# Pg6-Power_supply_3.net
KiCad netlist of a schematic drawn in Altium Designer
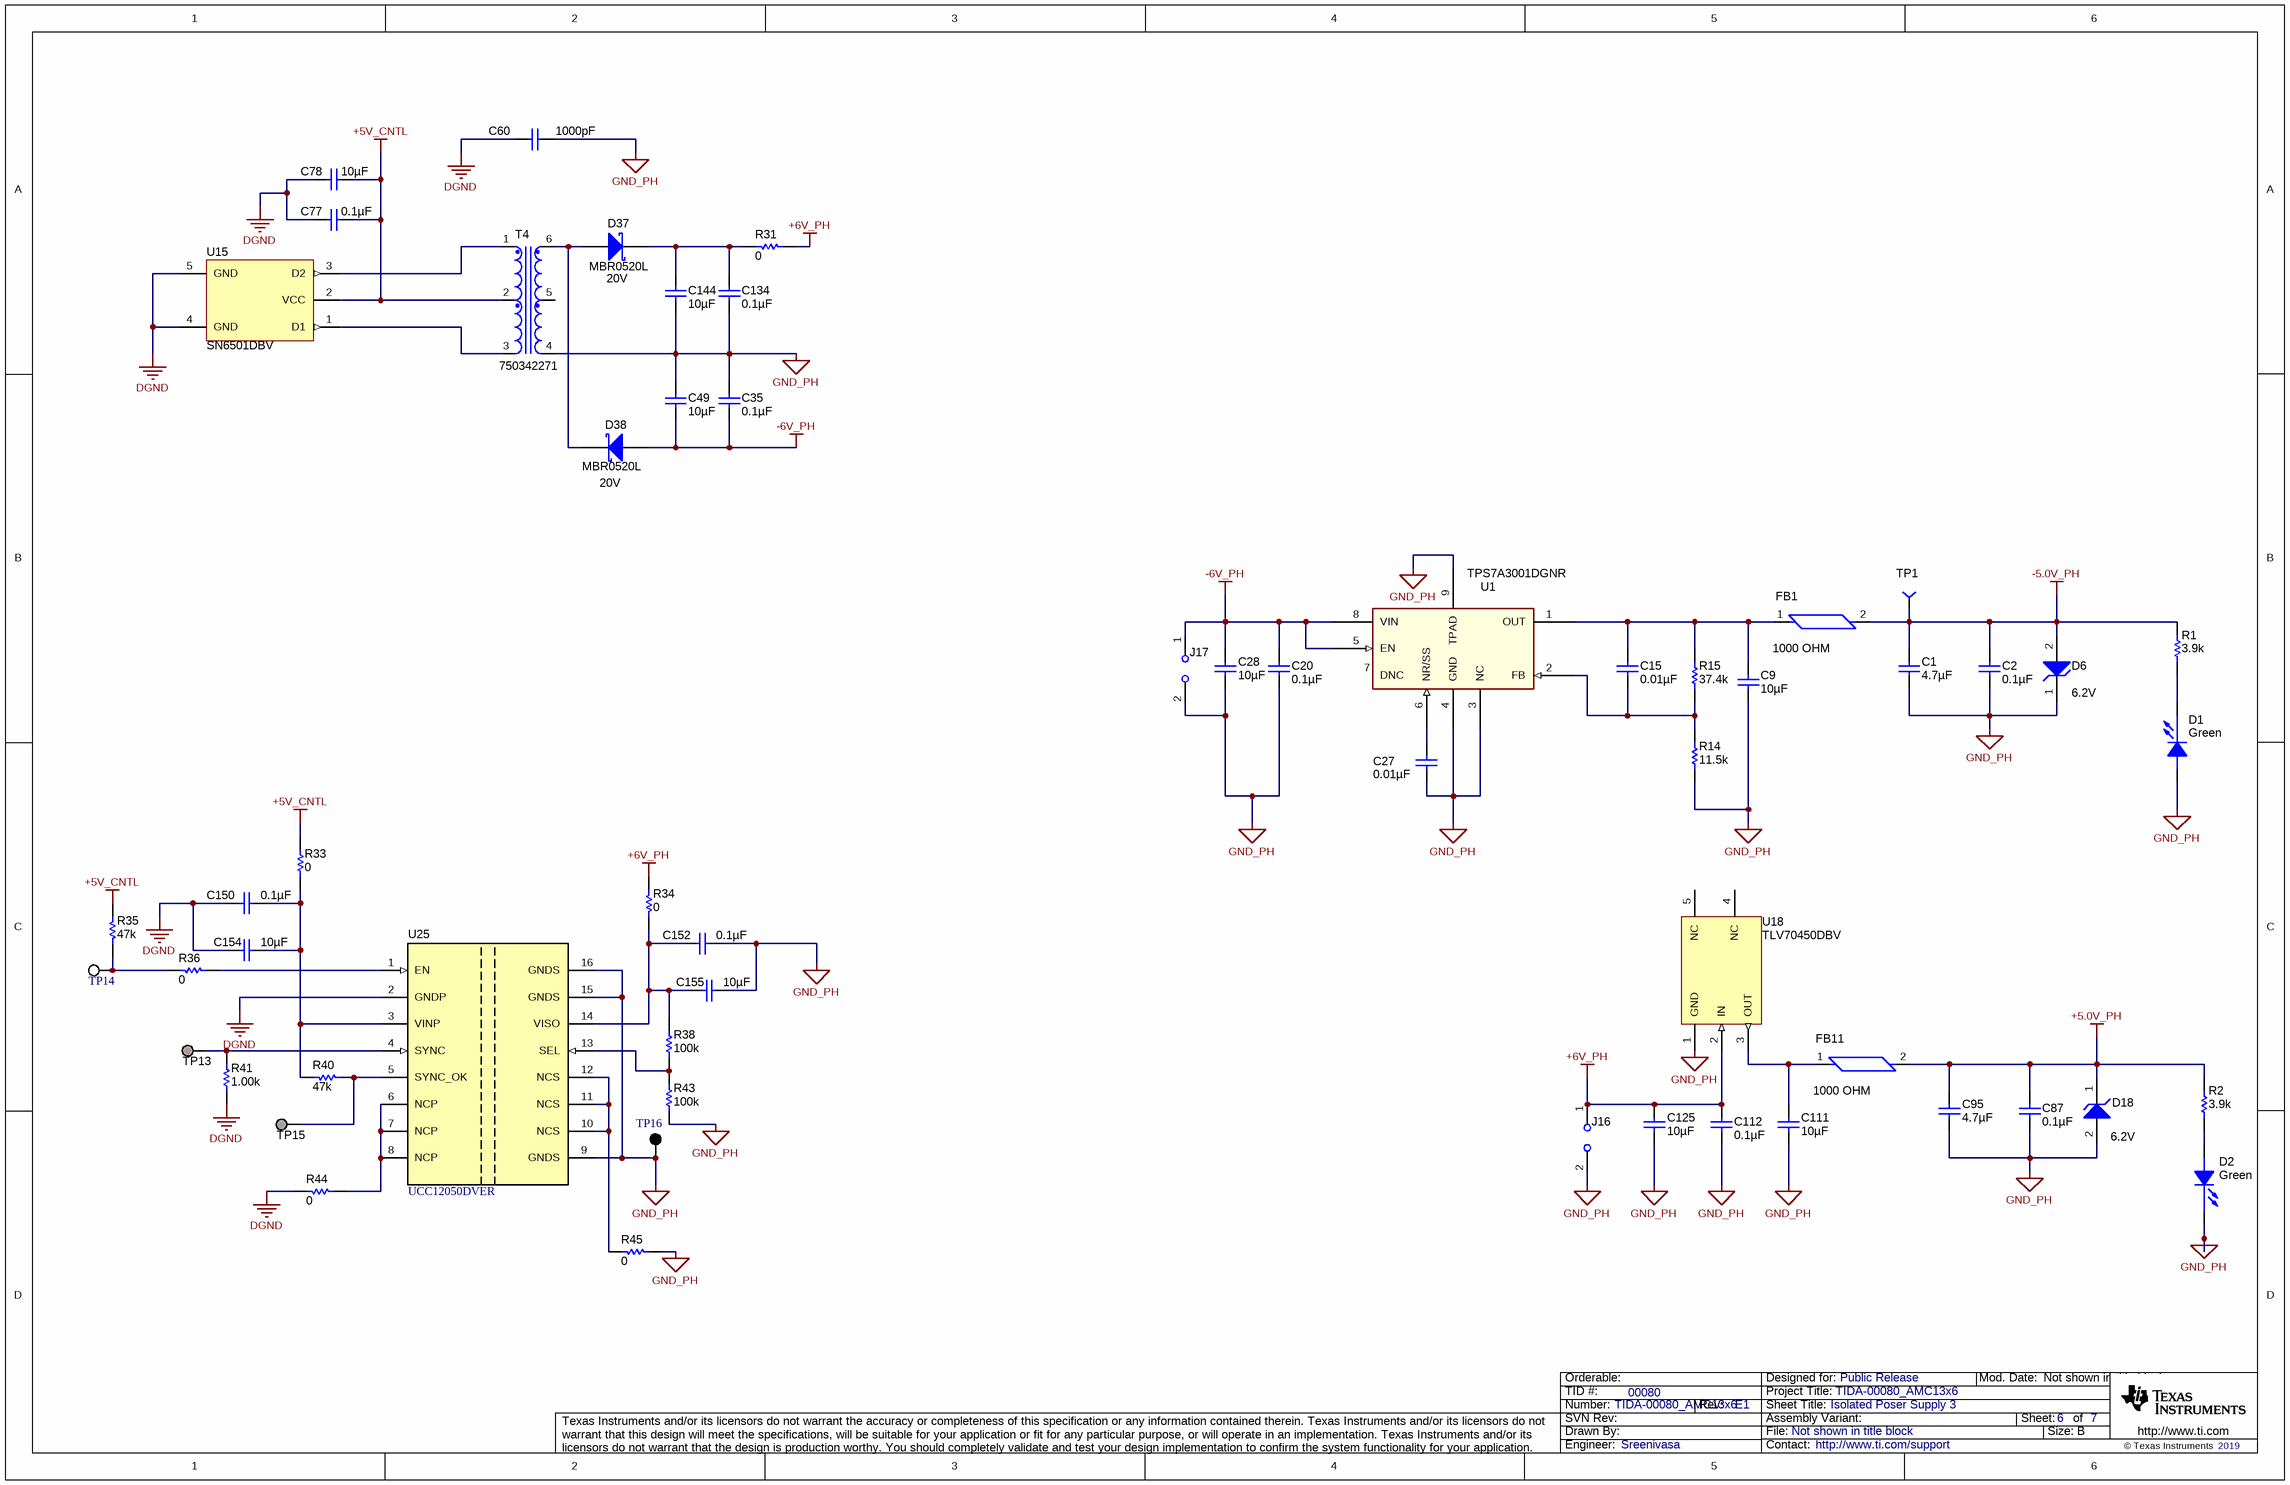
[diagram p0: Pg6-Power supply 3.SchDoc]

(export (version "E")
  (design (tool "Eeschema 10.0.6"))
  (components
    (comp (ref "C1")
      (value "~")
      (footprint "ISE_MCS_SDM_E1_20MAY:0805_HV")
      (description "CAP, CERM, 4.7uF, 50V, +/-10%, X5R, 0805")
      (fields
        (field (name "PARTNUMBER") "C2012X5R1H475K125AB")
        (field (name "VALUEDISPLAYED") "4.7µF")
        (field (name "MANUFACTURER") "TDK")
        (field (name "PUBLISHER") "Texas Instruments")
      )
      (libsource (lib "Capacitor_Ceramic") (part "C2012X5R1H475K125AB"))
    )
    (comp (ref "C2")
      (value "~")
      (footprint "ISE_MCS_SDM_E1_20MAY:0603")
      (description "CAP, CERM, 0.1uF, 50V, +/-10%, X7R, 0603")
      (fields
        (field (name "PARTNUMBER") "C0603C104K5RACTU")
        (field (name "VALUEDISPLAYED") "0.1µF")
        (field (name "MANUFACTURER") "Kemet")
        (field (name "PUBLISHER") "Texas Instruments")
      )
      (libsource (lib "Capacitor_Ceramic") (part "C0603C104K5RACTU"))
    )
    (comp (ref "C9")
      (value "~")
      (footprint "ISE_MCS_SDM_E1_20MAY:1210")
      (description "CAP, CERM, 10uF, 35V, +/-20%, X7R, 1210")
      (fields
        (field (name "PARTNUMBER") "GMK325AB7106MM-T")
        (field (name "VALUEDISPLAYED") "10µF")
        (field (name "MANUFACTURER") "Taiyo Yuden")
        (field (name "PUBLISHER") "Texas Instruments")
      )
      (libsource (lib "Capacitor_Ceramic") (part "GMK325AB7106MM-T"))
    )
    (comp (ref "C15")
      (value "~")
      (footprint "ISE_MCS_SDM_E1_20MAY:0603")
      (description "CAP, CERM, 0.01uF, 100V, +/-5%, X7R, 0603")
      (fields
        (field (name "PARTNUMBER") "06031C103J4Z4A")
        (field (name "VALUEDISPLAYED") "0.01µF")
        (field (name "MANUFACTURER") "AVX")
        (field (name "PUBLISHER") "Texas Instruments")
      )
      (libsource (lib "Capacitor_Ceramic") (part "06031C103J4Z4A"))
    )
    (comp (ref "C20")
      (value "~")
      (footprint "ISE_MCS_SDM_E1_20MAY:0603")
      (description "CAP, CERM, 0.1uF, 50V, +/-10%, X7R, 0603")
      (fields
        (field (name "PARTNUMBER") "C0603C104K5RACTU")
        (field (name "VALUEDISPLAYED") "0.1µF")
        (field (name "MANUFACTURER") "Kemet")
        (field (name "PUBLISHER") "Texas Instruments")
      )
      (libsource (lib "Capacitor_Ceramic") (part "C0603C104K5RACTU"))
    )
    (comp (ref "C27")
      (value "~")
      (footprint "ISE_MCS_SDM_E1_20MAY:0603")
      (description "CAP, CERM, 0.01uF, 100V, +/-5%, X7R, 0603")
      (fields
        (field (name "PARTNUMBER") "06031C103J4Z4A")
        (field (name "VALUEDISPLAYED") "0.01µF")
        (field (name "MANUFACTURER") "AVX")
        (field (name "PUBLISHER") "Texas Instruments")
      )
      (libsource (lib "Capacitor_Ceramic") (part "06031C103J4Z4A"))
    )
    (comp (ref "C28")
      (value "~")
      (footprint "ISE_MCS_SDM_E1_20MAY:1210")
      (description "CAP, CERM, 10uF, 35V, +/-20%, X7R, 1210")
      (fields
        (field (name "PARTNUMBER") "GMK325AB7106MM-T")
        (field (name "VALUEDISPLAYED") "10µF")
        (field (name "MANUFACTURER") "Taiyo Yuden")
        (field (name "PUBLISHER") "Texas Instruments")
      )
      (libsource (lib "Capacitor_Ceramic") (part "GMK325AB7106MM-T"))
    )
    (comp (ref "C35")
      (value "~")
      (footprint "ISE_MCS_SDM_E1_20MAY:0603")
      (description "CAP, CERM, 0.1uF, 50V, +/-10%, X7R, 0603")
      (fields
        (field (name "PARTNUMBER") "C0603C104K5RACTU")
        (field (name "VALUEDISPLAYED") "0.1µF")
        (field (name "MANUFACTURER") "Kemet")
        (field (name "PUBLISHER") "Texas Instruments")
      )
      (libsource (lib "Capacitor_Ceramic") (part "C0603C104K5RACTU"))
    )
    (comp (ref "C49")
      (value "~")
      (footprint "ISE_MCS_SDM_E1_20MAY:1210")
      (description "CAP, CERM, 10uF, 35V, +/-20%, X7R, 1210")
      (fields
        (field (name "PARTNUMBER") "GMK325AB7106MM-T")
        (field (name "VALUEDISPLAYED") "10µF")
        (field (name "MANUFACTURER") "Taiyo Yuden")
        (field (name "PUBLISHER") "Texas Instruments")
      )
      (libsource (lib "Capacitor_Ceramic") (part "GMK325AB7106MM-T"))
    )
    (comp (ref "C60")
      (value "1000pF")
      (footprint "CAP_200mil")
      (description "CAP CER 1000PF 1KV 10% RADIAL")
      (fields
        (field (name "PARTNUMBER") "S102K29Y5PN63J5R")
        (field (name "MANUFACTURER") "Vishay BC Components")
        (field (name "PUBLISHER") "Texas Instruments")
      )
      (libsource (lib "TI-INDIA-ALTIUM") (part "202R18W102KV4E"))
    )
    (comp (ref "C77")
      (value "~")
      (footprint "ISE_MCS_SDM_E1_20MAY:0603")
      (description "CAP, CERM, 0.1uF, 50V, +/-10%, X7R, 0603")
      (fields
        (field (name "PARTNUMBER") "C0603C104K5RACTU")
        (field (name "VALUEDISPLAYED") "0.1µF")
        (field (name "MANUFACTURER") "Kemet")
        (field (name "PUBLISHER") "Texas Instruments")
      )
      (libsource (lib "Capacitor_Ceramic") (part "C0603C104K5RACTU"))
    )
    (comp (ref "C78")
      (value "~")
      (footprint "ISE_MCS_SDM_E1_20MAY:1210")
      (description "CAP, CERM, 10uF, 35V, +/-20%, X7R, 1210")
      (fields
        (field (name "PARTNUMBER") "GMK325AB7106MM-T")
        (field (name "VALUEDISPLAYED") "10µF")
        (field (name "MANUFACTURER") "Taiyo Yuden")
        (field (name "PUBLISHER") "Texas Instruments")
      )
      (libsource (lib "Capacitor_Ceramic") (part "GMK325AB7106MM-T"))
    )
    (comp (ref "C87")
      (value "~")
      (footprint "ISE_MCS_SDM_E1_20MAY:0603")
      (description "CAP, CERM, 0.1uF, 50V, +/-10%, X7R, 0603")
      (fields
        (field (name "PARTNUMBER") "C0603C104K5RACTU")
        (field (name "VALUEDISPLAYED") "0.1µF")
        (field (name "MANUFACTURER") "Kemet")
        (field (name "PUBLISHER") "Texas Instruments")
      )
      (libsource (lib "Capacitor_Ceramic") (part "C0603C104K5RACTU"))
    )
    (comp (ref "C95")
      (value "~")
      (footprint "ISE_MCS_SDM_E1_20MAY:0805_HV")
      (description "CAP, CERM, 4.7uF, 50V, +/-10%, X5R, 0805")
      (fields
        (field (name "PARTNUMBER") "C2012X5R1H475K125AB")
        (field (name "VALUEDISPLAYED") "4.7µF")
        (field (name "MANUFACTURER") "TDK")
        (field (name "PUBLISHER") "Texas Instruments")
      )
      (libsource (lib "Capacitor_Ceramic") (part "C2012X5R1H475K125AB"))
    )
    (comp (ref "C111")
      (value "~")
      (footprint "ISE_MCS_SDM_E1_20MAY:1210")
      (description "CAP, CERM, 10uF, 35V, +/-20%, X7R, 1210")
      (fields
        (field (name "PARTNUMBER") "GMK325AB7106MM-T")
        (field (name "VALUEDISPLAYED") "10µF")
        (field (name "MANUFACTURER") "Taiyo Yuden")
        (field (name "PUBLISHER") "Texas Instruments")
      )
      (libsource (lib "Capacitor_Ceramic") (part "GMK325AB7106MM-T"))
    )
    (comp (ref "C112")
      (value "~")
      (footprint "ISE_MCS_SDM_E1_20MAY:0603")
      (description "CAP, CERM, 0.1uF, 50V, +/-10%, X7R, 0603")
      (fields
        (field (name "PARTNUMBER") "C0603C104K5RACTU")
        (field (name "VALUEDISPLAYED") "0.1µF")
        (field (name "MANUFACTURER") "Kemet")
        (field (name "PUBLISHER") "Texas Instruments")
      )
      (libsource (lib "Capacitor_Ceramic") (part "C0603C104K5RACTU"))
    )
    (comp (ref "C125")
      (value "~")
      (footprint "ISE_MCS_SDM_E1_20MAY:1210")
      (description "CAP, CERM, 10uF, 35V, +/-20%, X7R, 1210")
      (fields
        (field (name "PARTNUMBER") "GMK325AB7106MM-T")
        (field (name "VALUEDISPLAYED") "10µF")
        (field (name "MANUFACTURER") "Taiyo Yuden")
        (field (name "PUBLISHER") "Texas Instruments")
      )
      (libsource (lib "Capacitor_Ceramic") (part "GMK325AB7106MM-T"))
    )
    (comp (ref "C134")
      (value "~")
      (footprint "ISE_MCS_SDM_E1_20MAY:0603")
      (description "CAP, CERM, 0.1uF, 50V, +/-10%, X7R, 0603")
      (fields
        (field (name "PARTNUMBER") "C0603C104K5RACTU")
        (field (name "VALUEDISPLAYED") "0.1µF")
        (field (name "MANUFACTURER") "Kemet")
        (field (name "PUBLISHER") "Texas Instruments")
      )
      (libsource (lib "Capacitor_Ceramic") (part "C0603C104K5RACTU"))
    )
    (comp (ref "C144")
      (value "~")
      (footprint "ISE_MCS_SDM_E1_20MAY:1210")
      (description "CAP, CERM, 10uF, 35V, +/-20%, X7R, 1210")
      (fields
        (field (name "PARTNUMBER") "GMK325AB7106MM-T")
        (field (name "VALUEDISPLAYED") "10µF")
        (field (name "MANUFACTURER") "Taiyo Yuden")
        (field (name "PUBLISHER") "Texas Instruments")
      )
      (libsource (lib "Capacitor_Ceramic") (part "GMK325AB7106MM-T"))
    )
    (comp (ref "C150")
      (value "C0603C104K5RACTU")
      (footprint "0603")
      (description "CAP, CERM, 0.1uF, 50V, +/-10%, X7R, 0603")
      (fields
        (field (name "VALUEDISPLAYED") "0.1µF")
        (field (name "MANUFACTURER") "Kemet")
        (field (name "PUBLISHER") "Texas Instruments")
      )
      (libsource (lib "Capacitor_Ceramic") (part "C0603C104K5RACTU"))
    )
    (comp (ref "C152")
      (value "C0603C104K5RACTU")
      (footprint "0603")
      (description "CAP, CERM, 0.1uF, 50V, +/-10%, X7R, 0603")
      (fields
        (field (name "VALUEDISPLAYED") "0.1µF")
        (field (name "MANUFACTURER") "Kemet")
        (field (name "PUBLISHER") "Texas Instruments")
      )
      (libsource (lib "Capacitor_Ceramic") (part "C0603C104K5RACTU"))
    )
    (comp (ref "C154")
      (value "GRM31CR61H106KA12L")
      (footprint "1206_180")
      (description "CAP, CERM, 10 µF, 50 V, +/- 10%, X5R, 1206")
      (fields
        (field (name "VALUEDISPLAYED") "10µF")
        (field (name "MANUFACTURER") "MuRata")
        (field (name "PUBLISHER") "Texas Instruments")
      )
      (libsource (lib "Capacitor_Ceramic") (part "GRM31CR61H106KA12L"))
    )
    (comp (ref "C155")
      (value "GRM31CR61H106KA12L")
      (footprint "1206_180")
      (description "CAP, CERM, 10 µF, 50 V, +/- 10%, X5R, 1206")
      (fields
        (field (name "VALUEDISPLAYED") "10µF")
        (field (name "MANUFACTURER") "MuRata")
        (field (name "PUBLISHER") "Texas Instruments")
      )
      (libsource (lib "Capacitor_Ceramic") (part "GRM31CR61H106KA12L"))
    )
    (comp (ref "D1")
      (value "Green")
      (footprint "ISE_MCS_SDM_E1_20MAY:LED0603AA")
      (description "LED SmartLED Green 570NM")
      (fields
        (field (name "PARTNUMBER") "LG L29K-G2J1-24-Z")
        (field (name "MANUFACTURER") "OSRAM")
        (field (name "PUBLISHER") "TI")
        (field (name "SYMBOLCREATOR") "x0120606")
      )
      (libsource (lib "TI-INDIA-ALTIUM") (part "LED_LG L29K-G2J1-24-Z"))
    )
    (comp (ref "D2")
      (value "Green")
      (footprint "ISE_MCS_SDM_E1_20MAY:LED0603AA")
      (description "LED SmartLED Green 570NM")
      (fields
        (field (name "PARTNUMBER") "LG L29K-G2J1-24-Z")
        (field (name "MANUFACTURER") "OSRAM")
        (field (name "PUBLISHER") "TI")
        (field (name "SYMBOLCREATOR") "x0120606")
      )
      (libsource (lib "TI-INDIA-ALTIUM") (part "LED_LG L29K-G2J1-24-Z"))
    )
    (comp (ref "D6")
      (value "6.2V")
      (footprint "ISE_MCS_SDM_E1_20MAY:powerDI123")
      (description "Diode, Zener, 6.2V, 1W, PowerDI123")
      (fields
        (field (name "PARTNUMBER") "DFLZ6V2-7")
        (field (name "MANUFACTURER") "Diodes Inc.")
        (field (name "PUBLISHER") "Texas Instruments")
      )
      (libsource (lib "ZenerDiodes") (part "DFLZ6V2-7"))
    )
    (comp (ref "D18")
      (value "6.2V")
      (footprint "ISE_MCS_SDM_E1_20MAY:powerDI123")
      (description "Diode, Zener, 6.2V, 1W, PowerDI123")
      (fields
        (field (name "PARTNUMBER") "DFLZ6V2-7")
        (field (name "MANUFACTURER") "Diodes Inc.")
        (field (name "PUBLISHER") "Texas Instruments")
      )
      (libsource (lib "ZenerDiodes") (part "DFLZ6V2-7"))
    )
    (comp (ref "D37")
      (value "MBR0520L")
      (footprint "ISE_MCS_SDM_E1_20MAY:SOD-123")
      (description "Diode, Schottky, 20V, 0.5A, SOD-123")
      (fields
        (field (name "ALTIUM_VALUE") "20V")
        (field (name "MANUFACTURER") "Fairchild Semiconductor")
        (field (name "PUBLISHER") "Texas Instruments")
      )
      (libsource (lib "Diode") (part "MBR0520LT1G"))
    )
    (comp (ref "D38")
      (value "MBR0520L")
      (footprint "ISE_MCS_SDM_E1_20MAY:SOD-123")
      (description "Diode, Schottky, 20V, 0.5A, SOD-123")
      (fields
        (field (name "ALTIUM_VALUE") "20V")
        (field (name "MANUFACTURER") "Fairchild Semiconductor")
        (field (name "PUBLISHER") "Texas Instruments")
      )
      (libsource (lib "Diode") (part "MBR0520LT1G"))
    )
    (comp (ref "FB1")
      (value "1000 OHM")
      (footprint "ISE_MCS_SDM_E1_20MAY:FB0603")
      (description "FERRITE CHIP 1000 OHM 300MA 0603")
      (fields
        (field (name "PARTNUMBER") "MMZ1608B102C")
        (field (name "MANUFACTURER") "TDK Corporation")
        (field (name "PUBLISHER") "TI")
      )
      (libsource (lib "TI-INDIA-ALTIUM") (part "MMZ1608B102C"))
    )
    (comp (ref "FB11")
      (value "1000 OHM")
      (footprint "ISE_MCS_SDM_E1_20MAY:FB0603")
      (description "FERRITE CHIP 1000 OHM 300MA 0603")
      (fields
        (field (name "PARTNUMBER") "MMZ1608B102C")
        (field (name "MANUFACTURER") "TDK Corporation")
        (field (name "PUBLISHER") "TI")
      )
      (libsource (lib "TI-INDIA-ALTIUM") (part "MMZ1608B102C"))
    )
    (comp (ref "J16")
      (value "~")
      (footprint "ISE_MCS_SDM_E1_20MAY:HDR100_1X2")
      (description "Header, Male 2-pin, 100mil spacing,")
      (fields (field (name "MANUFACTURER") "FCI") (field (name "PARTNUMBER") "68001-402HLF"))
      (libsource (lib "PADSlegacy_Hardware") (part "JUMPER_2X100MIL"))
    )
    (comp (ref "J17")
      (value "~")
      (footprint "ISE_MCS_SDM_E1_20MAY:HDR100_1X2")
      (description "Header, Male 2-pin, 100mil spacing,")
      (fields (field (name "MANUFACTURER") "FCI") (field (name "PARTNUMBER") "68001-402HLF"))
      (libsource (lib "PADSlegacy_Hardware") (part "JUMPER_2X100MIL"))
    )
    (comp (ref "R1")
      (value "3.9k")
      (footprint "ISE_MCS_SDM_E1_20MAY:0603")
      (description "RES, 3.9k ohm, 5%, 0.1W, 0603")
      (fields
        (field (name "PARTNUMBER") "CRCW06033K90JNEA")
        (field (name "MANUFACTURER") "Vishay-Dale")
        (field (name "PUBLISHER") "Texas Instruments")
      )
      (libsource (lib "Resistor_0603") (part "CRCW06033K90JNEA"))
    )
    (comp (ref "R2")
      (value "3.9k")
      (footprint "ISE_MCS_SDM_E1_20MAY:0603")
      (description "RES, 3.9k ohm, 5%, 0.1W, 0603")
      (fields
        (field (name "PARTNUMBER") "CRCW06033K90JNEA")
        (field (name "MANUFACTURER") "Vishay-Dale")
        (field (name "PUBLISHER") "Texas Instruments")
      )
      (libsource (lib "Resistor_0603") (part "CRCW06033K90JNEA"))
    )
    (comp (ref "R14")
      (value "11.5k")
      (footprint "ISE_MCS_SDM_E1_20MAY:0603")
      (description "RES, 11.5k ohm, 1%, 0.1W, 0603")
      (fields
        (field (name "PARTNUMBER") "CRCW060311K5FKEA")
        (field (name "MANUFACTURER") "Vishay-Dale")
        (field (name "PUBLISHER") "Texas Instruments")
      )
      (libsource (lib "Resistor_0603") (part "CRCW060311K5FKEA"))
    )
    (comp (ref "R15")
      (value "37.4k")
      (footprint "ISE_MCS_SDM_E1_20MAY:0603")
      (description "RES 37.4K OHM 1/10W .1% 0603 SMD")
      (fields
        (field (name "PARTNUMBER") "ERA-3AEB3742V")
        (field (name "MANUFACTURER") "Panasonic")
        (field (name "PUBLISHER") "Texas Instruments")
      )
      (libsource (lib "Resistor_0603") (part "RT0603BRD0737KL"))
    )
    (comp (ref "R31")
      (value "0")
      (footprint "0402M")
      (description "RES, 0 ohm, 5%, 0.063W, 0402")
      (fields
        (field (name "PARTNUMBER") "RC0402JR-070RL")
        (field (name "MANUFACTURER") "Yageo America")
        (field (name "PUBLISHER") "Texas Instruments")
      )
      (libsource (lib "Resistor_0402") (part "RC0402JR-070RL"))
    )
    (comp (ref "R33")
      (value "CRCW06030000Z0EA")
      (footprint "0603")
      (description "RES, 0, 5%, 0.1 W, 0603")
      (fields
        (field (name "VALUEDISPLAYED") "0")
        (field (name "MANUFACTURER") "Vishay-Dale")
        (field (name "PUBLISHER") "Texas Instruments")
      )
      (libsource (lib "Resistor_0603") (part "CRCW06030000Z0EA"))
    )
    (comp (ref "R34")
      (value "CRCW06030000Z0EA")
      (footprint "0603")
      (description "RES, 0, 5%, 0.1 W, 0603")
      (fields
        (field (name "VALUEDISPLAYED") "0")
        (field (name "MANUFACTURER") "Vishay-Dale")
        (field (name "PUBLISHER") "Texas Instruments")
      )
      (libsource (lib "Resistor_0603") (part "CRCW06030000Z0EA"))
    )
    (comp (ref "R35")
      (value "RC0603JR-0747KL")
      (footprint "0603")
      (description "RES, 47 k, 5%, 0.1 W, 0603")
      (fields
        (field (name "VALUEDISPLAYED") "47k")
        (field (name "MANUFACTURER") "Yageo America")
        (field (name "PUBLISHER") "Texas Instruments")
      )
      (libsource (lib "Resistor_0603") (part "RC0603JR-0747KL"))
    )
    (comp (ref "R36")
      (value "0")
      (footprint "0402M")
      (description "RES, 0 ohm, 5%, 0.063W, 0402")
      (fields
        (field (name "PARTNUMBER") "RC0402JR-070RL")
        (field (name "MANUFACTURER") "Yageo America")
        (field (name "PUBLISHER") "Texas Instruments")
      )
      (libsource (lib "Resistor_0402") (part "RC0402JR-070RL"))
    )
    (comp (ref "R38")
      (value "CRCW0603100KFKEA")
      (footprint "0603")
      (description "RES, 100 k, 1%, 0.1 W, 0603")
      (fields
        (field (name "VALUEDISPLAYED") "100k")
        (field (name "MANUFACTURER") "Vishay-Dale")
        (field (name "PUBLISHER") "Texas Instruments")
      )
      (libsource (lib "Resistor_0603") (part "CRCW0603100KFKEA"))
    )
    (comp (ref "R40")
      (value "RC0603JR-0747KL")
      (footprint "0603")
      (description "RES, 47 k, 5%, 0.1 W, 0603")
      (fields
        (field (name "VALUEDISPLAYED") "47k")
        (field (name "MANUFACTURER") "Yageo America")
        (field (name "PUBLISHER") "Texas Instruments")
      )
      (libsource (lib "Resistor_0603") (part "RC0603JR-0747KL"))
    )
    (comp (ref "R41")
      (value "ERJ-2RKF1001X")
      (footprint "0402")
      (description "RES, 1.00 k, 1%, 0.1 W, 0402")
      (fields
        (field (name "VALUEDISPLAYED") "1.00k")
        (field (name "MANUFACTURER") "Panasonic")
        (field (name "PUBLISHER") "Texas Instruments")
      )
      (libsource (lib "Resistor_0402") (part "ERJ-2RKF1001X"))
    )
    (comp (ref "R43")
      (value "CRCW0603100KFKEA")
      (footprint "0603")
      (description "RES, 100 k, 1%, 0.1 W, 0603")
      (fields
        (field (name "VALUEDISPLAYED") "100k")
        (field (name "MANUFACTURER") "Vishay-Dale")
        (field (name "PUBLISHER") "Texas Instruments")
      )
      (libsource (lib "Resistor_0603") (part "CRCW0603100KFKEA"))
    )
    (comp (ref "R44")
      (value "0")
      (footprint "0402M")
      (description "RES, 0 ohm, 5%, 0.063W, 0402")
      (fields
        (field (name "PARTNUMBER") "RC0402JR-070RL")
        (field (name "MANUFACTURER") "Yageo America")
        (field (name "PUBLISHER") "Texas Instruments")
      )
      (libsource (lib "Resistor_0402") (part "RC0402JR-070RL"))
    )
    (comp (ref "R45")
      (value "0")
      (footprint "0402M")
      (description "RES, 0 ohm, 5%, 0.063W, 0402")
      (fields
        (field (name "PARTNUMBER") "RC0402JR-070RL")
        (field (name "MANUFACTURER") "Yageo America")
        (field (name "PUBLISHER") "Texas Instruments")
      )
      (libsource (lib "Resistor_0402") (part "RC0402JR-070RL"))
    )
    (comp (ref "T4")
      (value "750342271")
      (footprint "760390015")
      (description "Transformer 469uH SMD")
      (fields (field (name "MANUFACTURER") "Wurth Electronics Midcom") (field (name "PUBLISHER") "TI"))
      (libsource (lib "Isolated current sensing") (part "TRNSFMR"))
    )
    (comp (ref "TP1")
      (value "~")
      (footprint "ISE_MCS_SDM_E1_20MAY:TP-040_RND")
      (description "Test Point, O.040 Hole")
      (fields (field (name "MANUFACTURER") "STD"))
      (libsource (lib "PADSlegacy_Hardware") (part "TP-040_RND"))
    )
    (comp (ref "TP13")
      (value "Pogo Pad")
      (footprint "PogoPad")
      (description "Pad for Pogo Pin Connector")
      (fields (field (name "SYMBOLCREATOR") "codlsc") (field (name "PUBLISHER") "Texas Instruments"))
      (libsource (lib "MiscParts") (part "PogoPad"))
    )
    (comp (ref "TP14")
      (value "5002")
      (footprint "Keystone5002")
      (description "Test Point, Miniature, White, TH")
      (fields (field (name "MANUFACTURER") "Keystone") (field (name "PUBLISHER") "Texas Instruments"))
      (libsource (lib "Connectors_Keystone") (part "5002"))
    )
    (comp (ref "TP15")
      (value "Pogo Pad")
      (footprint "PogoPad")
      (description "Pad for Pogo Pin Connector")
      (fields (field (name "SYMBOLCREATOR") "codlsc") (field (name "PUBLISHER") "Texas Instruments"))
      (libsource (lib "MiscParts") (part "PogoPad"))
    )
    (comp (ref "TP16")
      (value "5001")
      (footprint "Keystone5001")
      (description "Test Point, Miniature, Black, TH")
      (fields (field (name "MANUFACTURER") "Keystone") (field (name "PUBLISHER") "Texas Instruments"))
      (libsource (lib "Connectors_Keystone") (part "5001"))
    )
    (comp (ref "U1")
      (value "~")
      (footprint "ISE_MCS_SDM_E1_20MAY:MSOP8(DGN)")
      (description "-36V, -200mA, Ultralow-Noise, Negative Linear Regulator")
      (fields
        (field (name "MANUFACTURER") "Texas Instruments")
        (field (name "PARTNUMBER") "TPS7A3001DGNR")
        (field (name "PUBLISHER") "Texas Instruments")
        (field (name "SYMBOLCREATOR") "x0120606")
      )
      (libsource (lib "TI-INDIA-ALTIUM") (part "TPS7A3001DGNR"))
    )
    (comp (ref "U15")
      (value "SN6501DBV")
      (footprint "ISE_MCS_SDM_E1_20MAY:DBV0005A_N")
      (description "Transformer Driver for Isolated Power Supplies, DBV0005A")
      (fields
        (field (name "MANUFACTURER") "Texas Instruments")
        (field (name "SYMBOLCREATOR") "a0411947")
        (field (name "PUBLISHER") "Texas Instruments")
      )
      (libsource (lib "TI_Pre_Release") (part "SN6501DBV"))
    )
    (comp (ref "U18")
      (value "TLV70450DBV")
      (footprint "ISE_MCS_SDM_E1_20MAY:DBV0005A_N")
      (description "Regulator, LDO, 5V, 0.15A, SOT23-5")
      (fields
        (field (name "MANUFACTURER") "Texas Instruments")
        (field (name "SYMBOLCREATOR") "x0120606")
        (field (name "PUBLISHER") "Texas Instruments")
      )
      (libsource (lib "TI-INDIA-ALTIUM") (part "TLV70450DBV"))
    )
    (comp (ref "U25")
      (value "UCC12050DVER")
      (footprint "DVE0016A")
      (description "500 mW, High-Efficiency, Low-Emissions, 5 kVRMS Isolated DC-DC Converter, DVE0016A (SO-MOD-16)")
      (fields
        (field (name "PARTNUMBER") "UCC12050DVER")
        (field (name "ALTERNATE PARTNUMBER") "UCC12050DVE")
        (field (name "MANUFACTURER") "Texas Instruments")
      )
      (libsource (lib "Altium Vault - TI") (part "UCC12050"))
    )
  )
  (nets
    (net (code "1") (name "+5.0V_PH") (class "Default")
      (node (ref "C87") (pin "1") (pinfunction "1_1") (pintype "passive"))
      (node (ref "C95") (pin "2") (pinfunction "2_2") (pintype "passive"))
      (node (ref "D18") (pin "1") (pinfunction "K_1") (pintype "passive"))
      (node (ref "FB11") (pin "2") (pinfunction "2_2") (pintype "passive"))
      (node (ref "R2") (pin "2") (pinfunction "2_2") (pintype "passive"))
    )
    (net (code "2") (name "+5V_CNTL") (class "Default")
      (node (ref "C77") (pin "2") (pinfunction "2_2") (pintype "passive"))
      (node (ref "C78") (pin "2") (pinfunction "2_2") (pintype "passive"))
      (node (ref "R33") (pin "2") (pinfunction "2_2") (pintype "passive"))
      (node (ref "R35") (pin "2") (pinfunction "2_2") (pintype "passive"))
      (node (ref "T4") (pin "2") (pinfunction "2_2") (pintype "passive"))
      (node (ref "U15") (pin "2") (pinfunction "VCC_2") (pintype "power_in"))
    )
    (net (code "3") (name "+6V_PH") (class "Default")
      (node (ref "C112") (pin "1") (pinfunction "1_1") (pintype "passive"))
      (node (ref "C125") (pin "2") (pinfunction "2_2") (pintype "passive"))
      (node (ref "J16") (pin "1") (pintype "passive"))
      (node (ref "R31") (pin "1") (pinfunction "1_1") (pintype "passive"))
      (node (ref "R34") (pin "2") (pinfunction "2_2") (pintype "passive"))
      (node (ref "U18") (pin "2") (pinfunction "IN_2") (pintype "input"))
    )
    (net (code "4") (name "-5.0V_PH") (class "Default")
      (node (ref "C1") (pin "2") (pinfunction "2_2") (pintype "passive"))
      (node (ref "C2") (pin "1") (pinfunction "1_1") (pintype "passive"))
      (node (ref "D6") (pin "2") (pinfunction "A_2") (pintype "passive"))
      (node (ref "FB1") (pin "2") (pinfunction "2_2") (pintype "passive"))
      (node (ref "R1") (pin "2") (pinfunction "2_2") (pintype "passive"))
      (node (ref "TP1") (pin "1") (pinfunction "1_1") (pintype "passive"))
    )
    (net (code "5") (name "-6V_PH") (class "Default")
      (node (ref "C20") (pin "1") (pinfunction "1_1") (pintype "passive"))
      (node (ref "C28") (pin "2") (pinfunction "2_2") (pintype "passive"))
      (node (ref "C35") (pin "2") (pinfunction "2_2") (pintype "passive"))
      (node (ref "C49") (pin "2") (pinfunction "2_2") (pintype "passive"))
      (node (ref "D38") (pin "2") (pinfunction "A_2") (pintype "passive"))
      (node (ref "J17") (pin "1") (pintype "passive"))
      (node (ref "U1") (pin "5") (pinfunction "EN_5") (pintype "input"))
      (node (ref "U1") (pin "8") (pinfunction "VIN_8") (pintype "power_in"))
    )
    (net (code "6") (name "DGND") (class "Default")
      (node (ref "C150") (pin "1") (pinfunction "1_1") (pintype "passive"))
      (node (ref "C154") (pin "2") (pinfunction "2_2") (pintype "passive"))
      (node (ref "C60") (pin "1") (pinfunction "1_1") (pintype "passive"))
      (node (ref "C77") (pin "1") (pinfunction "1_1") (pintype "passive"))
      (node (ref "C78") (pin "1") (pinfunction "1_1") (pintype "passive"))
      (node (ref "R41") (pin "1") (pinfunction "1_1") (pintype "passive"))
      (node (ref "R44") (pin "2") (pinfunction "2_2") (pintype "passive"))
      (node (ref "U15") (pin "4") (pinfunction "GND_4") (pintype "power_in"))
      (node (ref "U15") (pin "5") (pinfunction "GND_5") (pintype "power_in"))
      (node (ref "U25") (pin "2") (pinfunction "GNDP_2") (pintype "power_in"))
    )
    (net (code "7") (name "GND_PH") (class "Default")
      (node (ref "C1") (pin "1") (pinfunction "1_1") (pintype "passive"))
      (node (ref "C111") (pin "1") (pinfunction "1_1") (pintype "passive"))
      (node (ref "C112") (pin "2") (pinfunction "2_2") (pintype "passive"))
      (node (ref "C125") (pin "1") (pinfunction "1_1") (pintype "passive"))
      (node (ref "C134") (pin "2") (pinfunction "2_2") (pintype "passive"))
      (node (ref "C144") (pin "2") (pinfunction "2_2") (pintype "passive"))
      (node (ref "C152") (pin "1") (pinfunction "1_1") (pintype "passive"))
      (node (ref "C155") (pin "1") (pinfunction "1_1") (pintype "passive"))
      (node (ref "C2") (pin "2") (pinfunction "2_2") (pintype "passive"))
      (node (ref "C20") (pin "2") (pinfunction "2_2") (pintype "passive"))
      (node (ref "C27") (pin "1") (pinfunction "1_1") (pintype "passive"))
      (node (ref "C28") (pin "1") (pinfunction "1_1") (pintype "passive"))
      (node (ref "C35") (pin "1") (pinfunction "1_1") (pintype "passive"))
      (node (ref "C49") (pin "1") (pinfunction "1_1") (pintype "passive"))
      (node (ref "C60") (pin "2") (pinfunction "2_2") (pintype "passive"))
      (node (ref "C87") (pin "2") (pinfunction "2_2") (pintype "passive"))
      (node (ref "C9") (pin "1") (pinfunction "1_1") (pintype "passive"))
      (node (ref "C95") (pin "1") (pinfunction "1_1") (pintype "passive"))
      (node (ref "D1") (pin "2") (pinfunction "A_2") (pintype "passive"))
      (node (ref "D18") (pin "2") (pinfunction "A_2") (pintype "passive"))
      (node (ref "D2") (pin "1") (pinfunction "C_1") (pintype "passive"))
      (node (ref "D6") (pin "1") (pinfunction "K_1") (pintype "passive"))
      (node (ref "J16") (pin "2") (pintype "passive"))
      (node (ref "J17") (pin "2") (pintype "passive"))
      (node (ref "R14") (pin "1") (pinfunction "1_1") (pintype "passive"))
      (node (ref "R43") (pin "1") (pinfunction "1_1") (pintype "passive"))
      (node (ref "R45") (pin "1") (pinfunction "1_1") (pintype "passive"))
      (node (ref "T4") (pin "4") (pinfunction "4_4") (pintype "passive"))
      (node (ref "TP16") (pin "1") (pintype "passive"))
      (node (ref "U1") (pin "3") (pinfunction "NC_3") (pintype "passive"))
      (node (ref "U1") (pin "4") (pinfunction "GND_4") (pintype "power_in"))
      (node (ref "U1") (pin "9") (pinfunction "TPAD_9") (pintype "passive"))
      (node (ref "U18") (pin "1") (pinfunction "GND_1") (pintype "power_in"))
      (node (ref "U25") (pin "15") (pinfunction "GNDS_15") (pintype "power_in"))
      (node (ref "U25") (pin "16") (pinfunction "GNDS_16") (pintype "passive"))
      (node (ref "U25") (pin "9") (pinfunction "GNDS_9") (pintype "power_in"))
    )
    (net (code "8") (name "Net-(D1-C)") (class "Default")
      (node (ref "D1") (pin "1") (pinfunction "C_1") (pintype "passive"))
      (node (ref "R1") (pin "1") (pinfunction "1_1") (pintype "passive"))
    )
    (net (code "9") (name "Net-(D2-A)") (class "Default")
      (node (ref "D2") (pin "2") (pinfunction "A_2") (pintype "passive"))
      (node (ref "R2") (pin "1") (pinfunction "1_1") (pintype "passive"))
    )
    (net (code "10") (name "Net-(D37-A)") (class "Default")
      (node (ref "D37") (pin "2") (pinfunction "A_2") (pintype "passive"))
      (node (ref "D38") (pin "1") (pinfunction "K_1") (pintype "passive"))
      (node (ref "T4") (pin "6") (pinfunction "6_6") (pintype "passive"))
    )
    (net (code "11") (name "Net-(D37-K)") (class "Default")
      (node (ref "C134") (pin "1") (pinfunction "1_1") (pintype "passive"))
      (node (ref "C144") (pin "1") (pinfunction "1_1") (pintype "passive"))
      (node (ref "D37") (pin "1") (pinfunction "K_1") (pintype "passive"))
      (node (ref "R31") (pin "2") (pinfunction "2_2") (pintype "passive"))
    )
    (net (code "12") (name "Net-(R35-Pad1)") (class "Default")
      (node (ref "R35") (pin "1") (pinfunction "1_1") (pintype "passive"))
      (node (ref "R36") (pin "2") (pinfunction "2_2") (pintype "passive"))
      (node (ref "TP14") (pin "1") (pintype "passive"))
    )
    (net (code "13") (name "Net-(R44-Pad1)") (class "Default")
      (node (ref "R44") (pin "1") (pinfunction "1_1") (pintype "passive"))
      (node (ref "U25") (pin "6") (pinfunction "NCP_6") (pintype "passive"))
      (node (ref "U25") (pin "7") (pinfunction "NCP_7") (pintype "passive"))
      (node (ref "U25") (pin "8") (pinfunction "NCP_8") (pintype "passive"))
    )
    (net (code "14") (name "Net-(R45-Pad2)") (class "Default")
      (node (ref "R45") (pin "2") (pinfunction "2_2") (pintype "passive"))
      (node (ref "U25") (pin "10") (pinfunction "NCS_10") (pintype "passive"))
      (node (ref "U25") (pin "11") (pinfunction "NCS_11") (pintype "passive"))
      (node (ref "U25") (pin "12") (pinfunction "NCS_12") (pintype "passive"))
    )
    (net (code "15") (name "Net-(U1-FB)") (class "Default")
      (node (ref "C15") (pin "1") (pinfunction "1_1") (pintype "passive"))
      (node (ref "R14") (pin "2") (pinfunction "2_2") (pintype "passive"))
      (node (ref "R15") (pin "1") (pinfunction "1_1") (pintype "passive"))
      (node (ref "U1") (pin "2") (pinfunction "FB_2") (pintype "input"))
    )
    (net (code "16") (name "Net-(U1-NR{slash}SS)") (class "Default")
      (node (ref "C27") (pin "2") (pinfunction "2_2") (pintype "passive"))
      (node (ref "U1") (pin "6") (pinfunction "NR/SS_6") (pintype "input"))
    )
    (net (code "17") (name "Net-(U1-OUT)") (class "Default")
      (node (ref "C15") (pin "2") (pinfunction "2_2") (pintype "passive"))
      (node (ref "C9") (pin "2") (pinfunction "2_2") (pintype "passive"))
      (node (ref "FB1") (pin "1") (pinfunction "1_1") (pintype "passive"))
      (node (ref "R15") (pin "2") (pinfunction "2_2") (pintype "passive"))
      (node (ref "U1") (pin "1") (pinfunction "OUT_1") (pintype "power_in"))
    )
    (net (code "18") (name "Net-(U15-D1)") (class "Default")
      (node (ref "T4") (pin "3") (pinfunction "3_3") (pintype "passive"))
      (node (ref "U15") (pin "1") (pinfunction "D1_1") (pintype "output"))
    )
    (net (code "19") (name "Net-(U15-D2)") (class "Default")
      (node (ref "T4") (pin "1") (pinfunction "1_1") (pintype "passive"))
      (node (ref "U15") (pin "3") (pinfunction "D2_3") (pintype "output"))
    )
    (net (code "20") (name "Net-(U18-OUT)") (class "Default")
      (node (ref "C111") (pin "2") (pinfunction "2_2") (pintype "passive"))
      (node (ref "FB11") (pin "1") (pinfunction "1_1") (pintype "passive"))
      (node (ref "U18") (pin "3") (pinfunction "OUT_3") (pintype "output"))
    )
    (net (code "21") (name "Net-(U25-EN)") (class "Default")
      (node (ref "R36") (pin "1") (pinfunction "1_1") (pintype "passive"))
      (node (ref "U25") (pin "1") (pinfunction "EN_1") (pintype "input"))
    )
    (net (code "22") (name "Net-(U25-SEL)") (class "Default")
      (node (ref "R38") (pin "2") (pinfunction "2_2") (pintype "passive"))
      (node (ref "R43") (pin "2") (pinfunction "2_2") (pintype "passive"))
      (node (ref "U25") (pin "13") (pinfunction "SEL_13") (pintype "input"))
    )
    (net (code "23") (name "Net-(U25-SYNC)") (class "Default")
      (node (ref "R41") (pin "2") (pinfunction "2_2") (pintype "passive"))
      (node (ref "TP13") (pin "1") (pintype "passive"))
      (node (ref "U25") (pin "4") (pinfunction "SYNC_4") (pintype "input"))
    )
    (net (code "24") (name "Net-(U25-SYNC_OK)") (class "Default")
      (node (ref "R40") (pin "1") (pinfunction "1_1") (pintype "passive"))
      (node (ref "TP15") (pin "1") (pintype "passive"))
      (node (ref "U25") (pin "5") (pinfunction "SYNC_OK_5") (pintype "open_collector"))
    )
    (net (code "25") (name "Net-(U25-VINP)") (class "Default")
      (node (ref "C150") (pin "2") (pinfunction "2_2") (pintype "passive"))
      (node (ref "C154") (pin "1") (pinfunction "1_1") (pintype "passive"))
      (node (ref "R33") (pin "1") (pinfunction "1_1") (pintype "passive"))
      (node (ref "R40") (pin "2") (pinfunction "2_2") (pintype "passive"))
      (node (ref "U25") (pin "3") (pinfunction "VINP_3") (pintype "power_in"))
    )
    (net (code "26") (name "Net-(U25-VISO)") (class "Default")
      (node (ref "C152") (pin "2") (pinfunction "2_2") (pintype "passive"))
      (node (ref "C155") (pin "2") (pinfunction "2_2") (pintype "passive"))
      (node (ref "R34") (pin "1") (pinfunction "1_1") (pintype "passive"))
      (node (ref "R38") (pin "1") (pinfunction "1_1") (pintype "passive"))
      (node (ref "U25") (pin "14") (pinfunction "VISO_14") (pintype "power_in"))
    )
    (net (code "27") (name "unconnected-(T4-Pad5)") (class "Default")
      (node (ref "T4") (pin "5") (pinfunction "5_5") (pintype "passive"))
    )
    (net (code "28") (name "unconnected-(U1-DNC-Pad7)") (class "Default")
      (node (ref "U1") (pin "7") (pinfunction "DNC_7") (pintype "passive"))
    )
    (net (code "29") (name "unconnected-(U18-NC-Pad4)") (class "Default")
      (node (ref "U18") (pin "4") (pinfunction "NC_4") (pintype "power_in"))
    )
    (net (code "30") (name "unconnected-(U18-NC-Pad5)") (class "Default")
      (node (ref "U18") (pin "5") (pinfunction "NC_5") (pintype "power_in"))
    )
  )
)
